# gpio_board.net
KiCad netlist of a schematic drawn in EAGLE
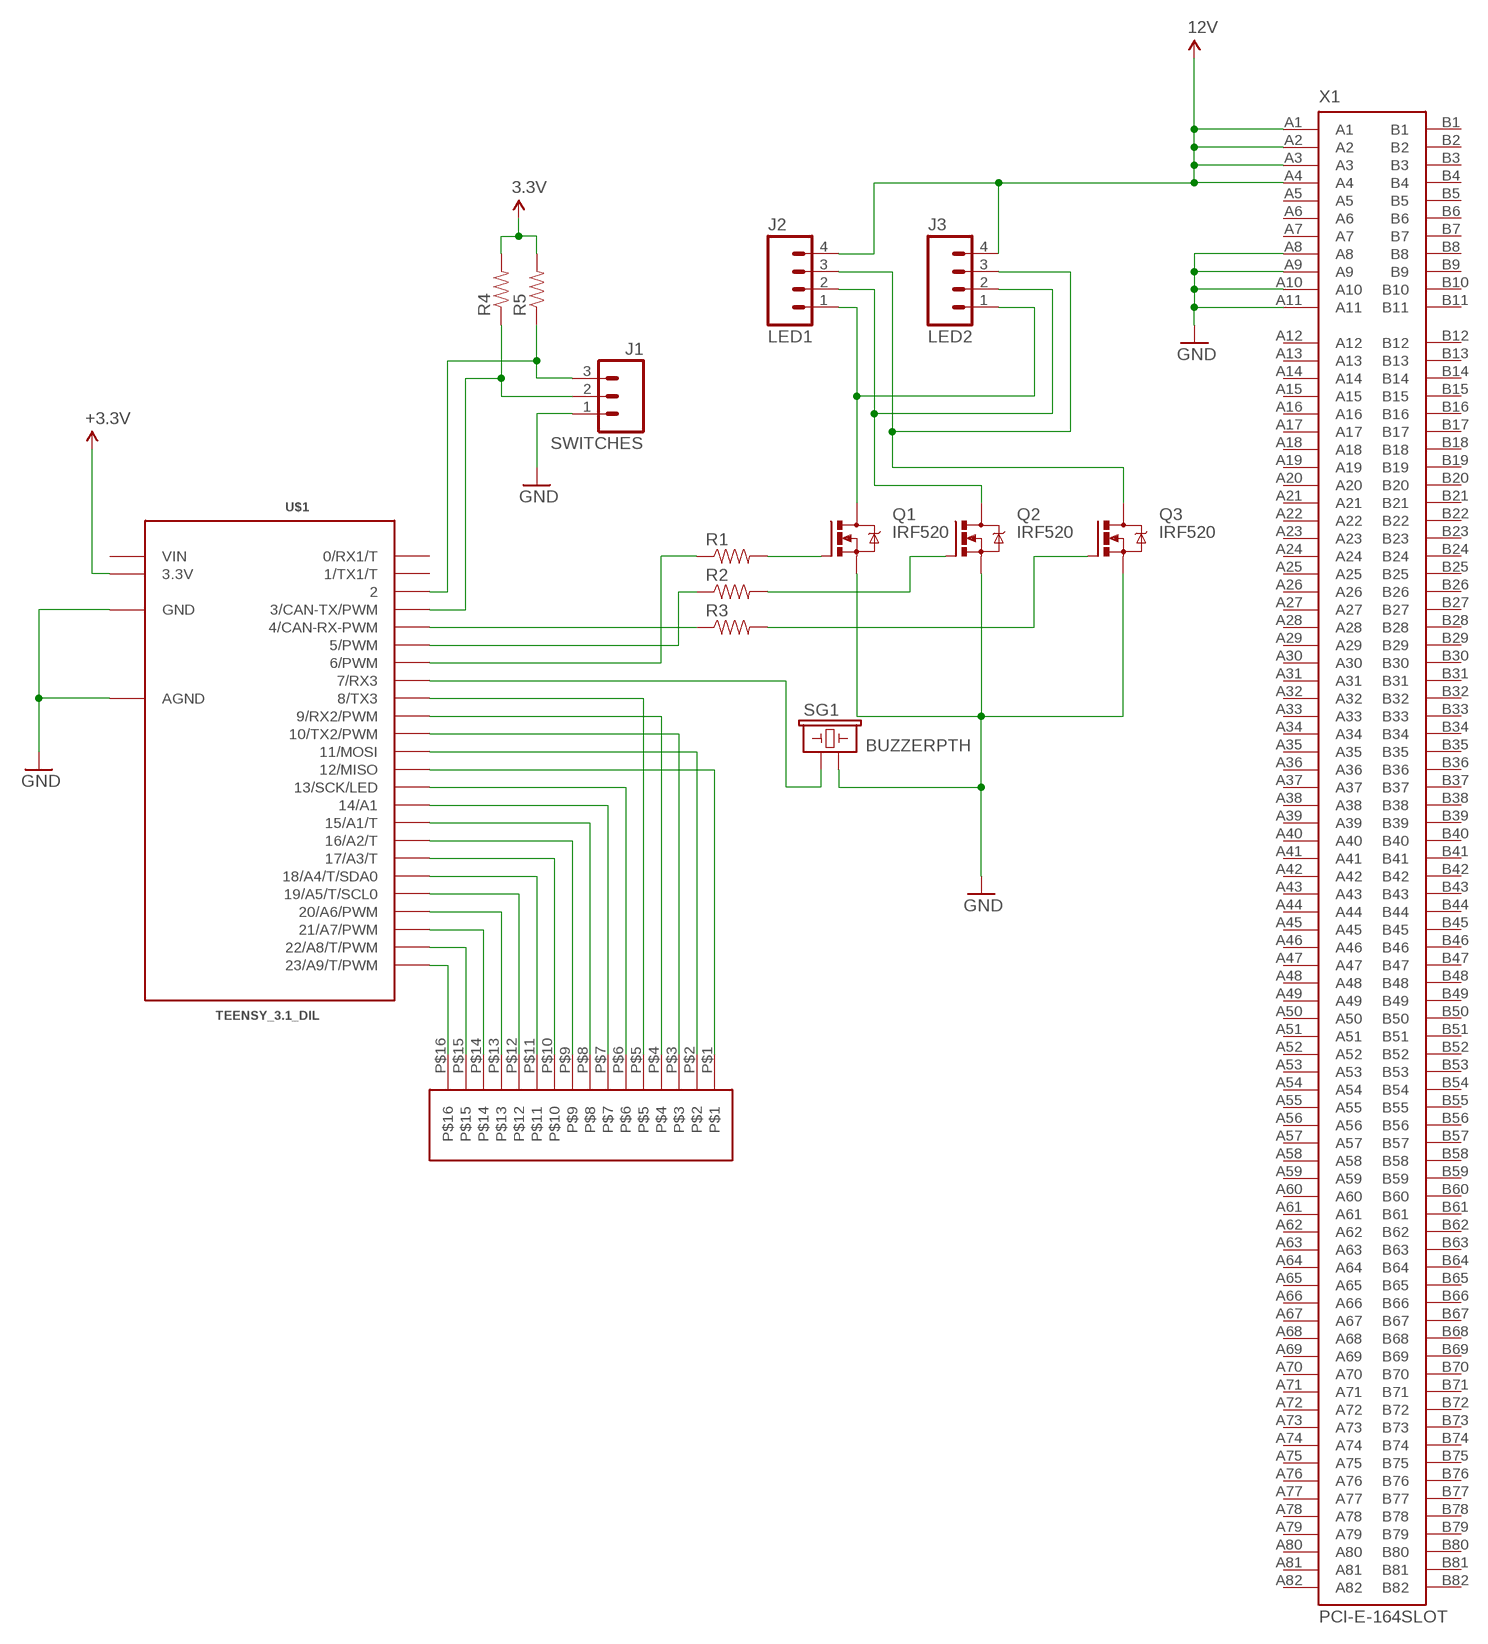
[diagram p0: schematic, sheet 1]

(export (version "E")
  (design (tool "Eeschema 10.0.6"))
  (components
    (comp (ref "J1")
      (value "SWITCHES")
      (footprint "eagle-import:1X03")
      (libsource (lib "eagle-import") (part "M03PTH"))
    )
    (comp (ref "J2")
      (value "LED1")
      (footprint "eagle-import:1X04")
      (libsource (lib "eagle-import") (part "M04PTH"))
    )
    (comp (ref "J3")
      (value "LED2")
      (footprint "eagle-import:1X04")
      (libsource (lib "eagle-import") (part "M04PTH"))
    )
    (comp (ref "Q1")
      (value "IRF520")
      (footprint "eagle-import:TO220BV")
      (libsource (lib "eagle-import") (part "IRF520"))
    )
    (comp (ref "Q2")
      (value "IRF520")
      (footprint "eagle-import:TO220BV")
      (libsource (lib "eagle-import") (part "IRF520"))
    )
    (comp (ref "Q3")
      (value "IRF520")
      (footprint "eagle-import:TO220BV")
      (libsource (lib "eagle-import") (part "IRF520"))
    )
    (comp (ref "R1")
      (value "RESISTOREZ")
      (footprint "eagle-import:AXIAL-0.3EZ")
      (libsource (lib "eagle-import") (part "RESISTOREZ"))
    )
    (comp (ref "R2")
      (value "RESISTOREZ")
      (footprint "eagle-import:AXIAL-0.3EZ")
      (libsource (lib "eagle-import") (part "RESISTOREZ"))
    )
    (comp (ref "R3")
      (value "RESISTOREZ")
      (footprint "eagle-import:AXIAL-0.3EZ")
      (libsource (lib "eagle-import") (part "RESISTOREZ"))
    )
    (comp (ref "R4")
      (value "RESISTOREZ")
      (footprint "eagle-import:AXIAL-0.3EZ")
      (libsource (lib "eagle-import") (part "RESISTOREZ"))
    )
    (comp (ref "R5")
      (value "RESISTOREZ")
      (footprint "eagle-import:AXIAL-0.3EZ")
      (libsource (lib "eagle-import") (part "RESISTOREZ"))
    )
    (comp (ref "SG1")
      (value "BUZZERPTH")
      (footprint "eagle-import:BUZZER-12MM")
      (libsource (lib "eagle-import") (part "BUZZERPTH"))
    )
    (comp (ref "U$1")
      (value "TEENSY_3.1_DIL")
      (footprint "eagle-import:TEENSY3-DIL")
      (libsource (lib "eagle-import") (part "TEENSY_3.1_DIL"))
    )
    (comp (ref "U$2")
      (value "PROTO_GRID")
      (footprint "eagle-import:PROTO_GRID16")
      (libsource (lib "eagle-import") (part "PROTO_GRID"))
    )
    (comp (ref "X1")
      (value "PCI-E-164SLOT")
      (footprint "eagle-import:PCI-E_SLOT")
      (libsource (lib "eagle-import") (part "PCI-E-164SLOT"))
    )
  )
  (nets
    (net (code "1") (name "+3.3V") (class "Default")
      (node (ref "J2") (pin "4") (pinfunction "4_4") (pintype "passive"))
      (node (ref "J3") (pin "4") (pinfunction "4_4") (pintype "passive"))
      (node (ref "U$1") (pin "3.3V") (pinfunction "3.3V_3.3V") (pintype "power_in"))
      (node (ref "X1") (pin "A1") (pinfunction "A1_A1") (pintype "passive"))
      (node (ref "X1") (pin "A2") (pinfunction "A2_A2") (pintype "passive"))
      (node (ref "X1") (pin "A3") (pinfunction "A3_A3") (pintype "passive"))
      (node (ref "X1") (pin "A4") (pinfunction "A4_A4") (pintype "passive"))
    )
    (net (code "2") (name "/VIN") (class "Default")
      (node (ref "U$1") (pin "VIN") (pinfunction "VIN_VIN") (pintype "power_in"))
    )
    (net (code "3") (name "3.3V") (class "Default")
      (node (ref "R4") (pin "P$2") (pinfunction "2_P$2") (pintype "passive"))
      (node (ref "R5") (pin "P$2") (pinfunction "2_P$2") (pintype "passive"))
    )
    (net (code "4") (name "GND") (class "Default")
      (node (ref "J1") (pin "1") (pinfunction "1_1") (pintype "passive"))
      (node (ref "Q1") (pin "S") (pinfunction "S_S") (pintype "passive"))
      (node (ref "Q2") (pin "S") (pinfunction "S_S") (pintype "passive"))
      (node (ref "Q3") (pin "S") (pinfunction "S_S") (pintype "passive"))
      (node (ref "SG1") (pin "-") (pinfunction "2_-") (pintype "passive"))
      (node (ref "U$1") (pin "AGND") (pinfunction "AGND_AGND") (pintype "power_in"))
      (node (ref "U$1") (pin "GND") (pinfunction "GND_GND") (pintype "power_in"))
      (node (ref "X1") (pin "A10") (pinfunction "A10_A10") (pintype "passive"))
      (node (ref "X1") (pin "A11") (pinfunction "A11_A11") (pintype "passive"))
      (node (ref "X1") (pin "A8") (pinfunction "A8_A8") (pintype "passive"))
      (node (ref "X1") (pin "A9") (pinfunction "A9_A9") (pintype "passive"))
    )
    (net (code "5") (name "Net-(J2-Pad1)") (class "Default")
      (node (ref "J2") (pin "1") (pinfunction "1_1") (pintype "passive"))
      (node (ref "J3") (pin "1") (pinfunction "1_1") (pintype "passive"))
      (node (ref "Q1") (pin "D") (pinfunction "D_D") (pintype "passive"))
    )
    (net (code "6") (name "Net-(J2-Pad2)") (class "Default")
      (node (ref "J2") (pin "2") (pinfunction "2_2") (pintype "passive"))
      (node (ref "J3") (pin "2") (pinfunction "2_2") (pintype "passive"))
      (node (ref "Q2") (pin "D") (pinfunction "D_D") (pintype "passive"))
    )
    (net (code "7") (name "Net-(J2-Pad3)") (class "Default")
      (node (ref "J2") (pin "3") (pinfunction "3_3") (pintype "passive"))
      (node (ref "J3") (pin "3") (pinfunction "3_3") (pintype "passive"))
      (node (ref "Q3") (pin "D") (pinfunction "D_D") (pintype "passive"))
    )
    (net (code "8") (name "Net-(R1-1)") (class "Default")
      (node (ref "R1") (pin "P$1") (pinfunction "1_P$1") (pintype "passive"))
      (node (ref "U$1") (pin "6") (pinfunction "6/PWM_6") (pintype "bidirectional"))
    )
    (net (code "9") (name "Net-(R1-2)") (class "Default")
      (node (ref "Q1") (pin "G") (pinfunction "G_G") (pintype "passive"))
      (node (ref "R1") (pin "P$2") (pinfunction "2_P$2") (pintype "passive"))
    )
    (net (code "10") (name "Net-(R2-1)") (class "Default")
      (node (ref "R2") (pin "P$1") (pinfunction "1_P$1") (pintype "passive"))
      (node (ref "U$1") (pin "5") (pinfunction "5/PWM_5") (pintype "bidirectional"))
    )
    (net (code "11") (name "Net-(R2-2)") (class "Default")
      (node (ref "Q2") (pin "G") (pinfunction "G_G") (pintype "passive"))
      (node (ref "R2") (pin "P$2") (pinfunction "2_P$2") (pintype "passive"))
    )
    (net (code "12") (name "Net-(R3-1)") (class "Default")
      (node (ref "R3") (pin "P$1") (pinfunction "1_P$1") (pintype "passive"))
      (node (ref "U$1") (pin "4") (pinfunction "4/CAN-RX-PWM_4") (pintype "bidirectional"))
    )
    (net (code "13") (name "Net-(R3-2)") (class "Default")
      (node (ref "Q3") (pin "G") (pinfunction "G_G") (pintype "passive"))
      (node (ref "R3") (pin "P$2") (pinfunction "2_P$2") (pintype "passive"))
    )
    (net (code "14") (name "Net-(R4-1)") (class "Default")
      (node (ref "J1") (pin "2") (pinfunction "2_2") (pintype "passive"))
      (node (ref "R4") (pin "P$1") (pinfunction "1_P$1") (pintype "passive"))
      (node (ref "U$1") (pin "3") (pinfunction "3/CAN-TX/PWM_3") (pintype "bidirectional"))
    )
    (net (code "15") (name "Net-(R5-1)") (class "Default")
      (node (ref "J1") (pin "3") (pinfunction "3_3") (pintype "passive"))
      (node (ref "R5") (pin "P$1") (pinfunction "1_P$1") (pintype "passive"))
      (node (ref "U$1") (pin "2") (pinfunction "2_2") (pintype "bidirectional"))
    )
    (net (code "16") (name "Net-(SG1-1)") (class "Default")
      (node (ref "SG1") (pin "+") (pinfunction "1_+") (pintype "passive"))
      (node (ref "U$1") (pin "7") (pinfunction "7/RX3_7") (pintype "bidirectional"))
    )
    (net (code "17") (name "Net-(U$1-8{slash}TX3)") (class "Default")
      (node (ref "U$1") (pin "8") (pinfunction "8/TX3_8") (pintype "bidirectional"))
      (node (ref "U$2") (pin "P$5") (pinfunction "P$5_P$5") (pintype "bidirectional"))
    )
    (net (code "18") (name "Net-(U$1-9{slash}RX2{slash}PWM)") (class "Default")
      (node (ref "U$1") (pin "9") (pinfunction "9/RX2/PWM_9") (pintype "bidirectional"))
      (node (ref "U$2") (pin "P$4") (pinfunction "P$4_P$4") (pintype "bidirectional"))
    )
    (net (code "19") (name "Net-(U$1-10{slash}TX2{slash}PWM)") (class "Default")
      (node (ref "U$1") (pin "10") (pinfunction "10/TX2/PWM_10") (pintype "bidirectional"))
      (node (ref "U$2") (pin "P$3") (pinfunction "P$3_P$3") (pintype "bidirectional"))
    )
    (net (code "20") (name "Net-(U$1-11{slash}MOSI)") (class "Default")
      (node (ref "U$1") (pin "11") (pinfunction "11/MOSI_11") (pintype "bidirectional"))
      (node (ref "U$2") (pin "P$2") (pinfunction "P$2_P$2") (pintype "bidirectional"))
    )
    (net (code "21") (name "Net-(U$1-12{slash}MISO)") (class "Default")
      (node (ref "U$1") (pin "12") (pinfunction "12/MISO_12") (pintype "bidirectional"))
      (node (ref "U$2") (pin "P$1") (pinfunction "P$1_P$1") (pintype "bidirectional"))
    )
    (net (code "22") (name "Net-(U$1-13{slash}SCK{slash}LED)") (class "Default")
      (node (ref "U$1") (pin "13") (pinfunction "13/SCK/LED_13") (pintype "bidirectional"))
      (node (ref "U$2") (pin "P$6") (pinfunction "P$6_P$6") (pintype "bidirectional"))
    )
    (net (code "23") (name "Net-(U$1-14{slash}A1)") (class "Default")
      (node (ref "U$1") (pin "14/A0") (pinfunction "14/A1_14/A0") (pintype "bidirectional"))
      (node (ref "U$2") (pin "P$7") (pinfunction "P$7_P$7") (pintype "bidirectional"))
    )
    (net (code "24") (name "Net-(U$1-15{slash}A1{slash}T)") (class "Default")
      (node (ref "U$1") (pin "15/A1") (pinfunction "15/A1/T_15/A1") (pintype "bidirectional"))
      (node (ref "U$2") (pin "P$8") (pinfunction "P$8_P$8") (pintype "bidirectional"))
    )
    (net (code "25") (name "Net-(U$1-16{slash}A2{slash}T)") (class "Default")
      (node (ref "U$1") (pin "16/A2") (pinfunction "16/A2/T_16/A2") (pintype "bidirectional"))
      (node (ref "U$2") (pin "P$9") (pinfunction "P$9_P$9") (pintype "bidirectional"))
    )
    (net (code "26") (name "Net-(U$1-17{slash}A3{slash}T)") (class "Default")
      (node (ref "U$1") (pin "17/A3") (pinfunction "17/A3/T_17/A3") (pintype "bidirectional"))
      (node (ref "U$2") (pin "P$10") (pinfunction "P$10_P$10") (pintype "bidirectional"))
    )
    (net (code "27") (name "Net-(U$1-18{slash}A4{slash}T{slash}SDA0)") (class "Default")
      (node (ref "U$1") (pin "18/A4") (pinfunction "18/A4/T/SDA0_18/A4") (pintype "bidirectional"))
      (node (ref "U$2") (pin "P$11") (pinfunction "P$11_P$11") (pintype "bidirectional"))
    )
    (net (code "28") (name "Net-(U$1-19{slash}A5{slash}T{slash}SCL0)") (class "Default")
      (node (ref "U$1") (pin "19/A5") (pinfunction "19/A5/T/SCL0_19/A5") (pintype "bidirectional"))
      (node (ref "U$2") (pin "P$12") (pinfunction "P$12_P$12") (pintype "bidirectional"))
    )
    (net (code "29") (name "Net-(U$1-20{slash}A6{slash}PWM)") (class "Default")
      (node (ref "U$1") (pin "20/A6") (pinfunction "20/A6/PWM_20/A6") (pintype "bidirectional"))
      (node (ref "U$2") (pin "P$13") (pinfunction "P$13_P$13") (pintype "bidirectional"))
    )
    (net (code "30") (name "Net-(U$1-21{slash}A7{slash}PWM)") (class "Default")
      (node (ref "U$1") (pin "21/A7") (pinfunction "21/A7/PWM_21/A7") (pintype "bidirectional"))
      (node (ref "U$2") (pin "P$14") (pinfunction "P$14_P$14") (pintype "bidirectional"))
    )
    (net (code "31") (name "Net-(U$1-22{slash}A8{slash}T{slash}PWM)") (class "Default")
      (node (ref "U$1") (pin "22/A8") (pinfunction "22/A8/T/PWM_22/A8") (pintype "bidirectional"))
      (node (ref "U$2") (pin "P$15") (pinfunction "P$15_P$15") (pintype "bidirectional"))
    )
    (net (code "32") (name "Net-(U$1-23{slash}A9{slash}T{slash}PWM)") (class "Default")
      (node (ref "U$1") (pin "23/A9") (pinfunction "23/A9/T/PWM_23/A9") (pintype "bidirectional"))
      (node (ref "U$2") (pin "P$16") (pinfunction "P$16_P$16") (pintype "bidirectional"))
    )
    (net (code "33") (name "unconnected-(U$1-0{slash}RX1{slash}T-Pad0)") (class "Default")
      (node (ref "U$1") (pin "0") (pinfunction "0/RX1/T_0") (pintype "bidirectional"))
    )
    (net (code "34") (name "unconnected-(U$1-1{slash}TX1{slash}T-Pad1)") (class "Default")
      (node (ref "U$1") (pin "1") (pinfunction "1/TX1/T_1") (pintype "bidirectional"))
    )
    (net (code "35") (name "unconnected-(X1-PadA5)") (class "Default")
      (node (ref "X1") (pin "A5") (pinfunction "A5_A5") (pintype "passive"))
    )
    (net (code "36") (name "unconnected-(X1-PadA6)") (class "Default")
      (node (ref "X1") (pin "A6") (pinfunction "A6_A6") (pintype "passive"))
    )
    (net (code "37") (name "unconnected-(X1-PadA7)") (class "Default")
      (node (ref "X1") (pin "A7") (pinfunction "A7_A7") (pintype "passive"))
    )
    (net (code "38") (name "unconnected-(X1-PadA12)") (class "Default")
      (node (ref "X1") (pin "A12") (pinfunction "A12_A12") (pintype "passive"))
    )
    (net (code "39") (name "unconnected-(X1-PadA13)") (class "Default")
      (node (ref "X1") (pin "A13") (pinfunction "A13_A13") (pintype "passive"))
    )
    (net (code "40") (name "unconnected-(X1-PadA14)") (class "Default")
      (node (ref "X1") (pin "A14") (pinfunction "A14_A14") (pintype "passive"))
    )
    (net (code "41") (name "unconnected-(X1-PadA15)") (class "Default")
      (node (ref "X1") (pin "A15") (pinfunction "A15_A15") (pintype "passive"))
    )
    (net (code "42") (name "unconnected-(X1-PadA16)") (class "Default")
      (node (ref "X1") (pin "A16") (pinfunction "A16_A16") (pintype "passive"))
    )
    (net (code "43") (name "unconnected-(X1-PadA17)") (class "Default")
      (node (ref "X1") (pin "A17") (pinfunction "A17_A17") (pintype "passive"))
    )
    (net (code "44") (name "unconnected-(X1-PadA18)") (class "Default")
      (node (ref "X1") (pin "A18") (pinfunction "A18_A18") (pintype "passive"))
    )
    (net (code "45") (name "unconnected-(X1-PadA19)") (class "Default")
      (node (ref "X1") (pin "A19") (pinfunction "A19_A19") (pintype "passive"))
    )
    (net (code "46") (name "unconnected-(X1-PadA20)") (class "Default")
      (node (ref "X1") (pin "A20") (pinfunction "A20_A20") (pintype "passive"))
    )
    (net (code "47") (name "unconnected-(X1-PadA21)") (class "Default")
      (node (ref "X1") (pin "A21") (pinfunction "A21_A21") (pintype "passive"))
    )
    (net (code "48") (name "unconnected-(X1-PadA22)") (class "Default")
      (node (ref "X1") (pin "A22") (pinfunction "A22_A22") (pintype "passive"))
    )
    (net (code "49") (name "unconnected-(X1-PadA23)") (class "Default")
      (node (ref "X1") (pin "A23") (pinfunction "A23_A23") (pintype "passive"))
    )
    (net (code "50") (name "unconnected-(X1-PadA24)") (class "Default")
      (node (ref "X1") (pin "A24") (pinfunction "A24_A24") (pintype "passive"))
    )
    (net (code "51") (name "unconnected-(X1-PadA25)") (class "Default")
      (node (ref "X1") (pin "A25") (pinfunction "A25_A25") (pintype "passive"))
    )
    (net (code "52") (name "unconnected-(X1-PadA26)") (class "Default")
      (node (ref "X1") (pin "A26") (pinfunction "A26_A26") (pintype "passive"))
    )
    (net (code "53") (name "unconnected-(X1-PadA27)") (class "Default")
      (node (ref "X1") (pin "A27") (pinfunction "A27_A27") (pintype "passive"))
    )
    (net (code "54") (name "unconnected-(X1-PadA28)") (class "Default")
      (node (ref "X1") (pin "A28") (pinfunction "A28_A28") (pintype "passive"))
    )
    (net (code "55") (name "unconnected-(X1-PadA29)") (class "Default")
      (node (ref "X1") (pin "A29") (pinfunction "A29_A29") (pintype "passive"))
    )
    (net (code "56") (name "unconnected-(X1-PadA30)") (class "Default")
      (node (ref "X1") (pin "A30") (pinfunction "A30_A30") (pintype "passive"))
    )
    (net (code "57") (name "unconnected-(X1-PadA31)") (class "Default")
      (node (ref "X1") (pin "A31") (pinfunction "A31_A31") (pintype "passive"))
    )
    (net (code "58") (name "unconnected-(X1-PadA32)") (class "Default")
      (node (ref "X1") (pin "A32") (pinfunction "A32_A32") (pintype "passive"))
    )
    (net (code "59") (name "unconnected-(X1-PadA33)") (class "Default")
      (node (ref "X1") (pin "A33") (pinfunction "A33_A33") (pintype "passive"))
    )
    (net (code "60") (name "unconnected-(X1-PadA34)") (class "Default")
      (node (ref "X1") (pin "A34") (pinfunction "A34_A34") (pintype "passive"))
    )
    (net (code "61") (name "unconnected-(X1-PadA35)") (class "Default")
      (node (ref "X1") (pin "A35") (pinfunction "A35_A35") (pintype "passive"))
    )
    (net (code "62") (name "unconnected-(X1-PadA36)") (class "Default")
      (node (ref "X1") (pin "A36") (pinfunction "A36_A36") (pintype "passive"))
    )
    (net (code "63") (name "unconnected-(X1-PadA37)") (class "Default")
      (node (ref "X1") (pin "A37") (pinfunction "A37_A37") (pintype "passive"))
    )
    (net (code "64") (name "unconnected-(X1-PadA38)") (class "Default")
      (node (ref "X1") (pin "A38") (pinfunction "A38_A38") (pintype "passive"))
    )
    (net (code "65") (name "unconnected-(X1-PadA39)") (class "Default")
      (node (ref "X1") (pin "A39") (pinfunction "A39_A39") (pintype "passive"))
    )
    (net (code "66") (name "unconnected-(X1-PadA40)") (class "Default")
      (node (ref "X1") (pin "A40") (pinfunction "A40_A40") (pintype "passive"))
    )
    (net (code "67") (name "unconnected-(X1-PadA41)") (class "Default")
      (node (ref "X1") (pin "A41") (pinfunction "A41_A41") (pintype "passive"))
    )
    (net (code "68") (name "unconnected-(X1-PadA42)") (class "Default")
      (node (ref "X1") (pin "A42") (pinfunction "A42_A42") (pintype "passive"))
    )
    (net (code "69") (name "unconnected-(X1-PadA43)") (class "Default")
      (node (ref "X1") (pin "A43") (pinfunction "A43_A43") (pintype "passive"))
    )
    (net (code "70") (name "unconnected-(X1-PadA44)") (class "Default")
      (node (ref "X1") (pin "A44") (pinfunction "A44_A44") (pintype "passive"))
    )
    (net (code "71") (name "unconnected-(X1-PadA45)") (class "Default")
      (node (ref "X1") (pin "A45") (pinfunction "A45_A45") (pintype "passive"))
    )
    (net (code "72") (name "unconnected-(X1-PadA46)") (class "Default")
      (node (ref "X1") (pin "A46") (pinfunction "A46_A46") (pintype "passive"))
    )
    (net (code "73") (name "unconnected-(X1-PadA47)") (class "Default")
      (node (ref "X1") (pin "A47") (pinfunction "A47_A47") (pintype "passive"))
    )
    (net (code "74") (name "unconnected-(X1-PadA48)") (class "Default")
      (node (ref "X1") (pin "A48") (pinfunction "A48_A48") (pintype "passive"))
    )
    (net (code "75") (name "unconnected-(X1-PadA49)") (class "Default")
      (node (ref "X1") (pin "A49") (pinfunction "A49_A49") (pintype "passive"))
    )
    (net (code "76") (name "unconnected-(X1-PadA50)") (class "Default")
      (node (ref "X1") (pin "A50") (pinfunction "A50_A50") (pintype "passive"))
    )
    (net (code "77") (name "unconnected-(X1-PadA51)") (class "Default")
      (node (ref "X1") (pin "A51") (pinfunction "A51_A51") (pintype "passive"))
    )
    (net (code "78") (name "unconnected-(X1-PadA52)") (class "Default")
      (node (ref "X1") (pin "A52") (pinfunction "A52_A52") (pintype "passive"))
    )
    (net (code "79") (name "unconnected-(X1-PadA53)") (class "Default")
      (node (ref "X1") (pin "A53") (pinfunction "A53_A53") (pintype "passive"))
    )
    (net (code "80") (name "unconnected-(X1-PadA54)") (class "Default")
      (node (ref "X1") (pin "A54") (pinfunction "A54_A54") (pintype "passive"))
    )
    (net (code "81") (name "unconnected-(X1-PadA55)") (class "Default")
      (node (ref "X1") (pin "A55") (pinfunction "A55_A55") (pintype "passive"))
    )
    (net (code "82") (name "unconnected-(X1-PadA56)") (class "Default")
      (node (ref "X1") (pin "A56") (pinfunction "A56_A56") (pintype "passive"))
    )
    (net (code "83") (name "unconnected-(X1-PadA57)") (class "Default")
      (node (ref "X1") (pin "A57") (pinfunction "A57_A57") (pintype "passive"))
    )
    (net (code "84") (name "unconnected-(X1-PadA58)") (class "Default")
      (node (ref "X1") (pin "A58") (pinfunction "A58_A58") (pintype "passive"))
    )
    (net (code "85") (name "unconnected-(X1-PadA59)") (class "Default")
      (node (ref "X1") (pin "A59") (pinfunction "A59_A59") (pintype "passive"))
    )
    (net (code "86") (name "unconnected-(X1-PadA60)") (class "Default")
      (node (ref "X1") (pin "A60") (pinfunction "A60_A60") (pintype "passive"))
    )
    (net (code "87") (name "unconnected-(X1-PadA61)") (class "Default")
      (node (ref "X1") (pin "A61") (pinfunction "A61_A61") (pintype "passive"))
    )
    (net (code "88") (name "unconnected-(X1-PadA62)") (class "Default")
      (node (ref "X1") (pin "A62") (pinfunction "A62_A62") (pintype "passive"))
    )
    (net (code "89") (name "unconnected-(X1-PadA63)") (class "Default")
      (node (ref "X1") (pin "A63") (pinfunction "A63_A63") (pintype "passive"))
    )
    (net (code "90") (name "unconnected-(X1-PadA64)") (class "Default")
      (node (ref "X1") (pin "A64") (pinfunction "A64_A64") (pintype "passive"))
    )
    (net (code "91") (name "unconnected-(X1-PadA65)") (class "Default")
      (node (ref "X1") (pin "A65") (pinfunction "A65_A65") (pintype "passive"))
    )
    (net (code "92") (name "unconnected-(X1-PadA66)") (class "Default")
      (node (ref "X1") (pin "A66") (pinfunction "A66_A66") (pintype "passive"))
    )
    (net (code "93") (name "unconnected-(X1-PadA67)") (class "Default")
      (node (ref "X1") (pin "A67") (pinfunction "A67_A67") (pintype "passive"))
    )
    (net (code "94") (name "unconnected-(X1-PadA68)") (class "Default")
      (node (ref "X1") (pin "A68") (pinfunction "A68_A68") (pintype "passive"))
    )
    (net (code "95") (name "unconnected-(X1-PadA69)") (class "Default")
      (node (ref "X1") (pin "A69") (pinfunction "A69_A69") (pintype "passive"))
    )
    (net (code "96") (name "unconnected-(X1-PadA70)") (class "Default")
      (node (ref "X1") (pin "A70") (pinfunction "A70_A70") (pintype "passive"))
    )
    (net (code "97") (name "unconnected-(X1-PadA71)") (class "Default")
      (node (ref "X1") (pin "A71") (pinfunction "A71_A71") (pintype "passive"))
    )
    (net (code "98") (name "unconnected-(X1-PadA72)") (class "Default")
      (node (ref "X1") (pin "A72") (pinfunction "A72_A72") (pintype "passive"))
    )
    (net (code "99") (name "unconnected-(X1-PadA73)") (class "Default")
      (node (ref "X1") (pin "A73") (pinfunction "A73_A73") (pintype "passive"))
    )
    (net (code "100") (name "unconnected-(X1-PadA74)") (class "Default")
      (node (ref "X1") (pin "A74") (pinfunction "A74_A74") (pintype "passive"))
    )
    (net (code "101") (name "unconnected-(X1-PadA75)") (class "Default")
      (node (ref "X1") (pin "A75") (pinfunction "A75_A75") (pintype "passive"))
    )
    (net (code "102") (name "unconnected-(X1-PadA76)") (class "Default")
      (node (ref "X1") (pin "A76") (pinfunction "A76_A76") (pintype "passive"))
    )
    (net (code "103") (name "unconnected-(X1-PadA77)") (class "Default")
      (node (ref "X1") (pin "A77") (pinfunction "A77_A77") (pintype "passive"))
    )
    (net (code "104") (name "unconnected-(X1-PadA78)") (class "Default")
      (node (ref "X1") (pin "A78") (pinfunction "A78_A78") (pintype "passive"))
    )
    (net (code "105") (name "unconnected-(X1-PadA79)") (class "Default")
      (node (ref "X1") (pin "A79") (pinfunction "A79_A79") (pintype "passive"))
    )
    (net (code "106") (name "unconnected-(X1-PadA80)") (class "Default")
      (node (ref "X1") (pin "A80") (pinfunction "A80_A80") (pintype "passive"))
    )
    (net (code "107") (name "unconnected-(X1-PadA81)") (class "Default")
      (node (ref "X1") (pin "A81") (pinfunction "A81_A81") (pintype "passive"))
    )
    (net (code "108") (name "unconnected-(X1-PadA82)") (class "Default")
      (node (ref "X1") (pin "A82") (pinfunction "A82_A82") (pintype "passive"))
    )
    (net (code "109") (name "unconnected-(X1-PadB1)") (class "Default")
      (node (ref "X1") (pin "B1") (pinfunction "B1_B1") (pintype "passive"))
    )
    (net (code "110") (name "unconnected-(X1-PadB2)") (class "Default")
      (node (ref "X1") (pin "B2") (pinfunction "B2_B2") (pintype "passive"))
    )
    (net (code "111") (name "unconnected-(X1-PadB3)") (class "Default")
      (node (ref "X1") (pin "B3") (pinfunction "B3_B3") (pintype "passive"))
    )
    (net (code "112") (name "unconnected-(X1-PadB4)") (class "Default")
      (node (ref "X1") (pin "B4") (pinfunction "B4_B4") (pintype "passive"))
    )
    (net (code "113") (name "unconnected-(X1-PadB5)") (class "Default")
      (node (ref "X1") (pin "B5") (pinfunction "B5_B5") (pintype "passive"))
    )
    (net (code "114") (name "unconnected-(X1-PadB6)") (class "Default")
      (node (ref "X1") (pin "B6") (pinfunction "B6_B6") (pintype "passive"))
    )
    (net (code "115") (name "unconnected-(X1-PadB7)") (class "Default")
      (node (ref "X1") (pin "B7") (pinfunction "B7_B7") (pintype "passive"))
    )
    (net (code "116") (name "unconnected-(X1-PadB8)") (class "Default")
      (node (ref "X1") (pin "B8") (pinfunction "B8_B8") (pintype "passive"))
    )
    (net (code "117") (name "unconnected-(X1-PadB9)") (class "Default")
      (node (ref "X1") (pin "B9") (pinfunction "B9_B9") (pintype "passive"))
    )
    (net (code "118") (name "unconnected-(X1-PadB10)") (class "Default")
      (node (ref "X1") (pin "B10") (pinfunction "B10_B10") (pintype "passive"))
    )
    (net (code "119") (name "unconnected-(X1-PadB11)") (class "Default")
      (node (ref "X1") (pin "B11") (pinfunction "B11_B11") (pintype "passive"))
    )
    (net (code "120") (name "unconnected-(X1-PadB12)") (class "Default")
      (node (ref "X1") (pin "B12") (pinfunction "B12_B12") (pintype "passive"))
    )
    (net (code "121") (name "unconnected-(X1-PadB13)") (class "Default")
      (node (ref "X1") (pin "B13") (pinfunction "B13_B13") (pintype "passive"))
    )
    (net (code "122") (name "unconnected-(X1-PadB14)") (class "Default")
      (node (ref "X1") (pin "B14") (pinfunction "B14_B14") (pintype "passive"))
    )
    (net (code "123") (name "unconnected-(X1-PadB15)") (class "Default")
      (node (ref "X1") (pin "B15") (pinfunction "B15_B15") (pintype "passive"))
    )
    (net (code "124") (name "unconnected-(X1-PadB16)") (class "Default")
      (node (ref "X1") (pin "B16") (pinfunction "B16_B16") (pintype "passive"))
    )
    (net (code "125") (name "unconnected-(X1-PadB17)") (class "Default")
      (node (ref "X1") (pin "B17") (pinfunction "B17_B17") (pintype "passive"))
    )
    (net (code "126") (name "unconnected-(X1-PadB18)") (class "Default")
      (node (ref "X1") (pin "B18") (pinfunction "B18_B18") (pintype "passive"))
    )
    (net (code "127") (name "unconnected-(X1-PadB19)") (class "Default")
      (node (ref "X1") (pin "B19") (pinfunction "B19_B19") (pintype "passive"))
    )
    (net (code "128") (name "unconnected-(X1-PadB20)") (class "Default")
      (node (ref "X1") (pin "B20") (pinfunction "B20_B20") (pintype "passive"))
    )
    (net (code "129") (name "unconnected-(X1-PadB21)") (class "Default")
      (node (ref "X1") (pin "B21") (pinfunction "B21_B21") (pintype "passive"))
    )
    (net (code "130") (name "unconnected-(X1-PadB22)") (class "Default")
      (node (ref "X1") (pin "B22") (pinfunction "B22_B22") (pintype "passive"))
    )
    (net (code "131") (name "unconnected-(X1-PadB23)") (class "Default")
      (node (ref "X1") (pin "B23") (pinfunction "B23_B23") (pintype "passive"))
    )
    (net (code "132") (name "unconnected-(X1-PadB24)") (class "Default")
      (node (ref "X1") (pin "B24") (pinfunction "B24_B24") (pintype "passive"))
    )
    (net (code "133") (name "unconnected-(X1-PadB25)") (class "Default")
      (node (ref "X1") (pin "B25") (pinfunction "B25_B25") (pintype "passive"))
    )
    (net (code "134") (name "unconnected-(X1-PadB26)") (class "Default")
      (node (ref "X1") (pin "B26") (pinfunction "B26_B26") (pintype "passive"))
    )
    (net (code "135") (name "unconnected-(X1-PadB27)") (class "Default")
      (node (ref "X1") (pin "B27") (pinfunction "B27_B27") (pintype "passive"))
    )
    (net (code "136") (name "unconnected-(X1-PadB28)") (class "Default")
      (node (ref "X1") (pin "B28") (pinfunction "B28_B28") (pintype "passive"))
    )
    (net (code "137") (name "unconnected-(X1-PadB29)") (class "Default")
      (node (ref "X1") (pin "B29") (pinfunction "B29_B29") (pintype "passive"))
    )
    (net (code "138") (name "unconnected-(X1-PadB30)") (class "Default")
      (node (ref "X1") (pin "B30") (pinfunction "B30_B30") (pintype "passive"))
    )
    (net (code "139") (name "unconnected-(X1-PadB31)") (class "Default")
      (node (ref "X1") (pin "B31") (pinfunction "B31_B31") (pintype "passive"))
    )
    (net (code "140") (name "unconnected-(X1-PadB32)") (class "Default")
      (node (ref "X1") (pin "B32") (pinfunction "B32_B32") (pintype "passive"))
    )
    (net (code "141") (name "unconnected-(X1-PadB33)") (class "Default")
      (node (ref "X1") (pin "B33") (pinfunction "B33_B33") (pintype "passive"))
    )
    (net (code "142") (name "unconnected-(X1-PadB34)") (class "Default")
      (node (ref "X1") (pin "B34") (pinfunction "B34_B34") (pintype "passive"))
    )
    (net (code "143") (name "unconnected-(X1-PadB35)") (class "Default")
      (node (ref "X1") (pin "B35") (pinfunction "B35_B35") (pintype "passive"))
    )
    (net (code "144") (name "unconnected-(X1-PadB36)") (class "Default")
      (node (ref "X1") (pin "B36") (pinfunction "B36_B36") (pintype "passive"))
    )
    (net (code "145") (name "unconnected-(X1-PadB37)") (class "Default")
      (node (ref "X1") (pin "B37") (pinfunction "B37_B37") (pintype "passive"))
    )
    (net (code "146") (name "unconnected-(X1-PadB38)") (class "Default")
      (node (ref "X1") (pin "B38") (pinfunction "B38_B38") (pintype "passive"))
    )
    (net (code "147") (name "unconnected-(X1-PadB39)") (class "Default")
      (node (ref "X1") (pin "B39") (pinfunction "B39_B39") (pintype "passive"))
    )
    (net (code "148") (name "unconnected-(X1-PadB40)") (class "Default")
      (node (ref "X1") (pin "B40") (pinfunction "B40_B40") (pintype "passive"))
    )
    (net (code "149") (name "unconnected-(X1-PadB41)") (class "Default")
      (node (ref "X1") (pin "B41") (pinfunction "B41_B41") (pintype "passive"))
    )
    (net (code "150") (name "unconnected-(X1-PadB42)") (class "Default")
      (node (ref "X1") (pin "B42") (pinfunction "B42_B42") (pintype "passive"))
    )
    (net (code "151") (name "unconnected-(X1-PadB43)") (class "Default")
      (node (ref "X1") (pin "B43") (pinfunction "B43_B43") (pintype "passive"))
    )
    (net (code "152") (name "unconnected-(X1-PadB44)") (class "Default")
      (node (ref "X1") (pin "B44") (pinfunction "B44_B44") (pintype "passive"))
    )
    (net (code "153") (name "unconnected-(X1-PadB45)") (class "Default")
      (node (ref "X1") (pin "B45") (pinfunction "B45_B45") (pintype "passive"))
    )
    (net (code "154") (name "unconnected-(X1-PadB46)") (class "Default")
      (node (ref "X1") (pin "B46") (pinfunction "B46_B46") (pintype "passive"))
    )
    (net (code "155") (name "unconnected-(X1-PadB47)") (class "Default")
      (node (ref "X1") (pin "B47") (pinfunction "B47_B47") (pintype "passive"))
    )
    (net (code "156") (name "unconnected-(X1-PadB48)") (class "Default")
      (node (ref "X1") (pin "B48") (pinfunction "B48_B48") (pintype "passive"))
    )
    (net (code "157") (name "unconnected-(X1-PadB49)") (class "Default")
      (node (ref "X1") (pin "B49") (pinfunction "B49_B49") (pintype "passive"))
    )
    (net (code "158") (name "unconnected-(X1-PadB50)") (class "Default")
      (node (ref "X1") (pin "B50") (pinfunction "B50_B50") (pintype "passive"))
    )
    (net (code "159") (name "unconnected-(X1-PadB51)") (class "Default")
      (node (ref "X1") (pin "B51") (pinfunction "B51_B51") (pintype "passive"))
    )
    (net (code "160") (name "unconnected-(X1-PadB52)") (class "Default")
      (node (ref "X1") (pin "B52") (pinfunction "B52_B52") (pintype "passive"))
    )
    (net (code "161") (name "unconnected-(X1-PadB53)") (class "Default")
      (node (ref "X1") (pin "B53") (pinfunction "B53_B53") (pintype "passive"))
    )
    (net (code "162") (name "unconnected-(X1-PadB54)") (class "Default")
      (node (ref "X1") (pin "B54") (pinfunction "B54_B54") (pintype "passive"))
    )
    (net (code "163") (name "unconnected-(X1-PadB55)") (class "Default")
      (node (ref "X1") (pin "B55") (pinfunction "B55_B55") (pintype "passive"))
    )
    (net (code "164") (name "unconnected-(X1-PadB56)") (class "Default")
      (node (ref "X1") (pin "B56") (pinfunction "B56_B56") (pintype "passive"))
    )
    (net (code "165") (name "unconnected-(X1-PadB57)") (class "Default")
      (node (ref "X1") (pin "B57") (pinfunction "B57_B57") (pintype "passive"))
    )
    (net (code "166") (name "unconnected-(X1-PadB58)") (class "Default")
      (node (ref "X1") (pin "B58") (pinfunction "B58_B58") (pintype "passive"))
    )
    (net (code "167") (name "unconnected-(X1-PadB59)") (class "Default")
      (node (ref "X1") (pin "B59") (pinfunction "B59_B59") (pintype "passive"))
    )
    (net (code "168") (name "unconnected-(X1-PadB60)") (class "Default")
      (node (ref "X1") (pin "B60") (pinfunction "B60_B60") (pintype "passive"))
    )
    (net (code "169") (name "unconnected-(X1-PadB61)") (class "Default")
      (node (ref "X1") (pin "B61") (pinfunction "B61_B61") (pintype "passive"))
    )
    (net (code "170") (name "unconnected-(X1-PadB62)") (class "Default")
      (node (ref "X1") (pin "B62") (pinfunction "B62_B62") (pintype "passive"))
    )
    (net (code "171") (name "unconnected-(X1-PadB63)") (class "Default")
      (node (ref "X1") (pin "B63") (pinfunction "B63_B63") (pintype "passive"))
    )
    (net (code "172") (name "unconnected-(X1-PadB64)") (class "Default")
      (node (ref "X1") (pin "B64") (pinfunction "B64_B64") (pintype "passive"))
    )
    (net (code "173") (name "unconnected-(X1-PadB65)") (class "Default")
      (node (ref "X1") (pin "B65") (pinfunction "B65_B65") (pintype "passive"))
    )
    (net (code "174") (name "unconnected-(X1-PadB66)") (class "Default")
      (node (ref "X1") (pin "B66") (pinfunction "B66_B66") (pintype "passive"))
    )
    (net (code "175") (name "unconnected-(X1-PadB67)") (class "Default")
      (node (ref "X1") (pin "B67") (pinfunction "B67_B67") (pintype "passive"))
    )
    (net (code "176") (name "unconnected-(X1-PadB68)") (class "Default")
      (node (ref "X1") (pin "B68") (pinfunction "B68_B68") (pintype "passive"))
    )
    (net (code "177") (name "unconnected-(X1-PadB69)") (class "Default")
      (node (ref "X1") (pin "B69") (pinfunction "B69_B69") (pintype "passive"))
    )
    (net (code "178") (name "unconnected-(X1-PadB70)") (class "Default")
      (node (ref "X1") (pin "B70") (pinfunction "B70_B70") (pintype "passive"))
    )
    (net (code "179") (name "unconnected-(X1-PadB71)") (class "Default")
      (node (ref "X1") (pin "B71") (pinfunction "B71_B71") (pintype "passive"))
    )
    (net (code "180") (name "unconnected-(X1-PadB72)") (class "Default")
      (node (ref "X1") (pin "B72") (pinfunction "B72_B72") (pintype "passive"))
    )
    (net (code "181") (name "unconnected-(X1-PadB73)") (class "Default")
      (node (ref "X1") (pin "B73") (pinfunction "B73_B73") (pintype "passive"))
    )
    (net (code "182") (name "unconnected-(X1-PadB74)") (class "Default")
      (node (ref "X1") (pin "B74") (pinfunction "B74_B74") (pintype "passive"))
    )
    (net (code "183") (name "unconnected-(X1-PadB75)") (class "Default")
      (node (ref "X1") (pin "B75") (pinfunction "B75_B75") (pintype "passive"))
    )
    (net (code "184") (name "unconnected-(X1-PadB76)") (class "Default")
      (node (ref "X1") (pin "B76") (pinfunction "B76_B76") (pintype "passive"))
    )
    (net (code "185") (name "unconnected-(X1-PadB77)") (class "Default")
      (node (ref "X1") (pin "B77") (pinfunction "B77_B77") (pintype "passive"))
    )
    (net (code "186") (name "unconnected-(X1-PadB78)") (class "Default")
      (node (ref "X1") (pin "B78") (pinfunction "B78_B78") (pintype "passive"))
    )
    (net (code "187") (name "unconnected-(X1-PadB79)") (class "Default")
      (node (ref "X1") (pin "B79") (pinfunction "B79_B79") (pintype "passive"))
    )
    (net (code "188") (name "unconnected-(X1-PadB80)") (class "Default")
      (node (ref "X1") (pin "B80") (pinfunction "B80_B80") (pintype "passive"))
    )
    (net (code "189") (name "unconnected-(X1-PadB81)") (class "Default")
      (node (ref "X1") (pin "B81") (pinfunction "B81_B81") (pintype "passive"))
    )
    (net (code "190") (name "unconnected-(X1-PadB82)") (class "Default")
      (node (ref "X1") (pin "B82") (pinfunction "B82_B82") (pintype "passive"))
    )
  )
)
